# Ethernet_0.net
KiCad netlist of a schematic drawn in Altium Designer
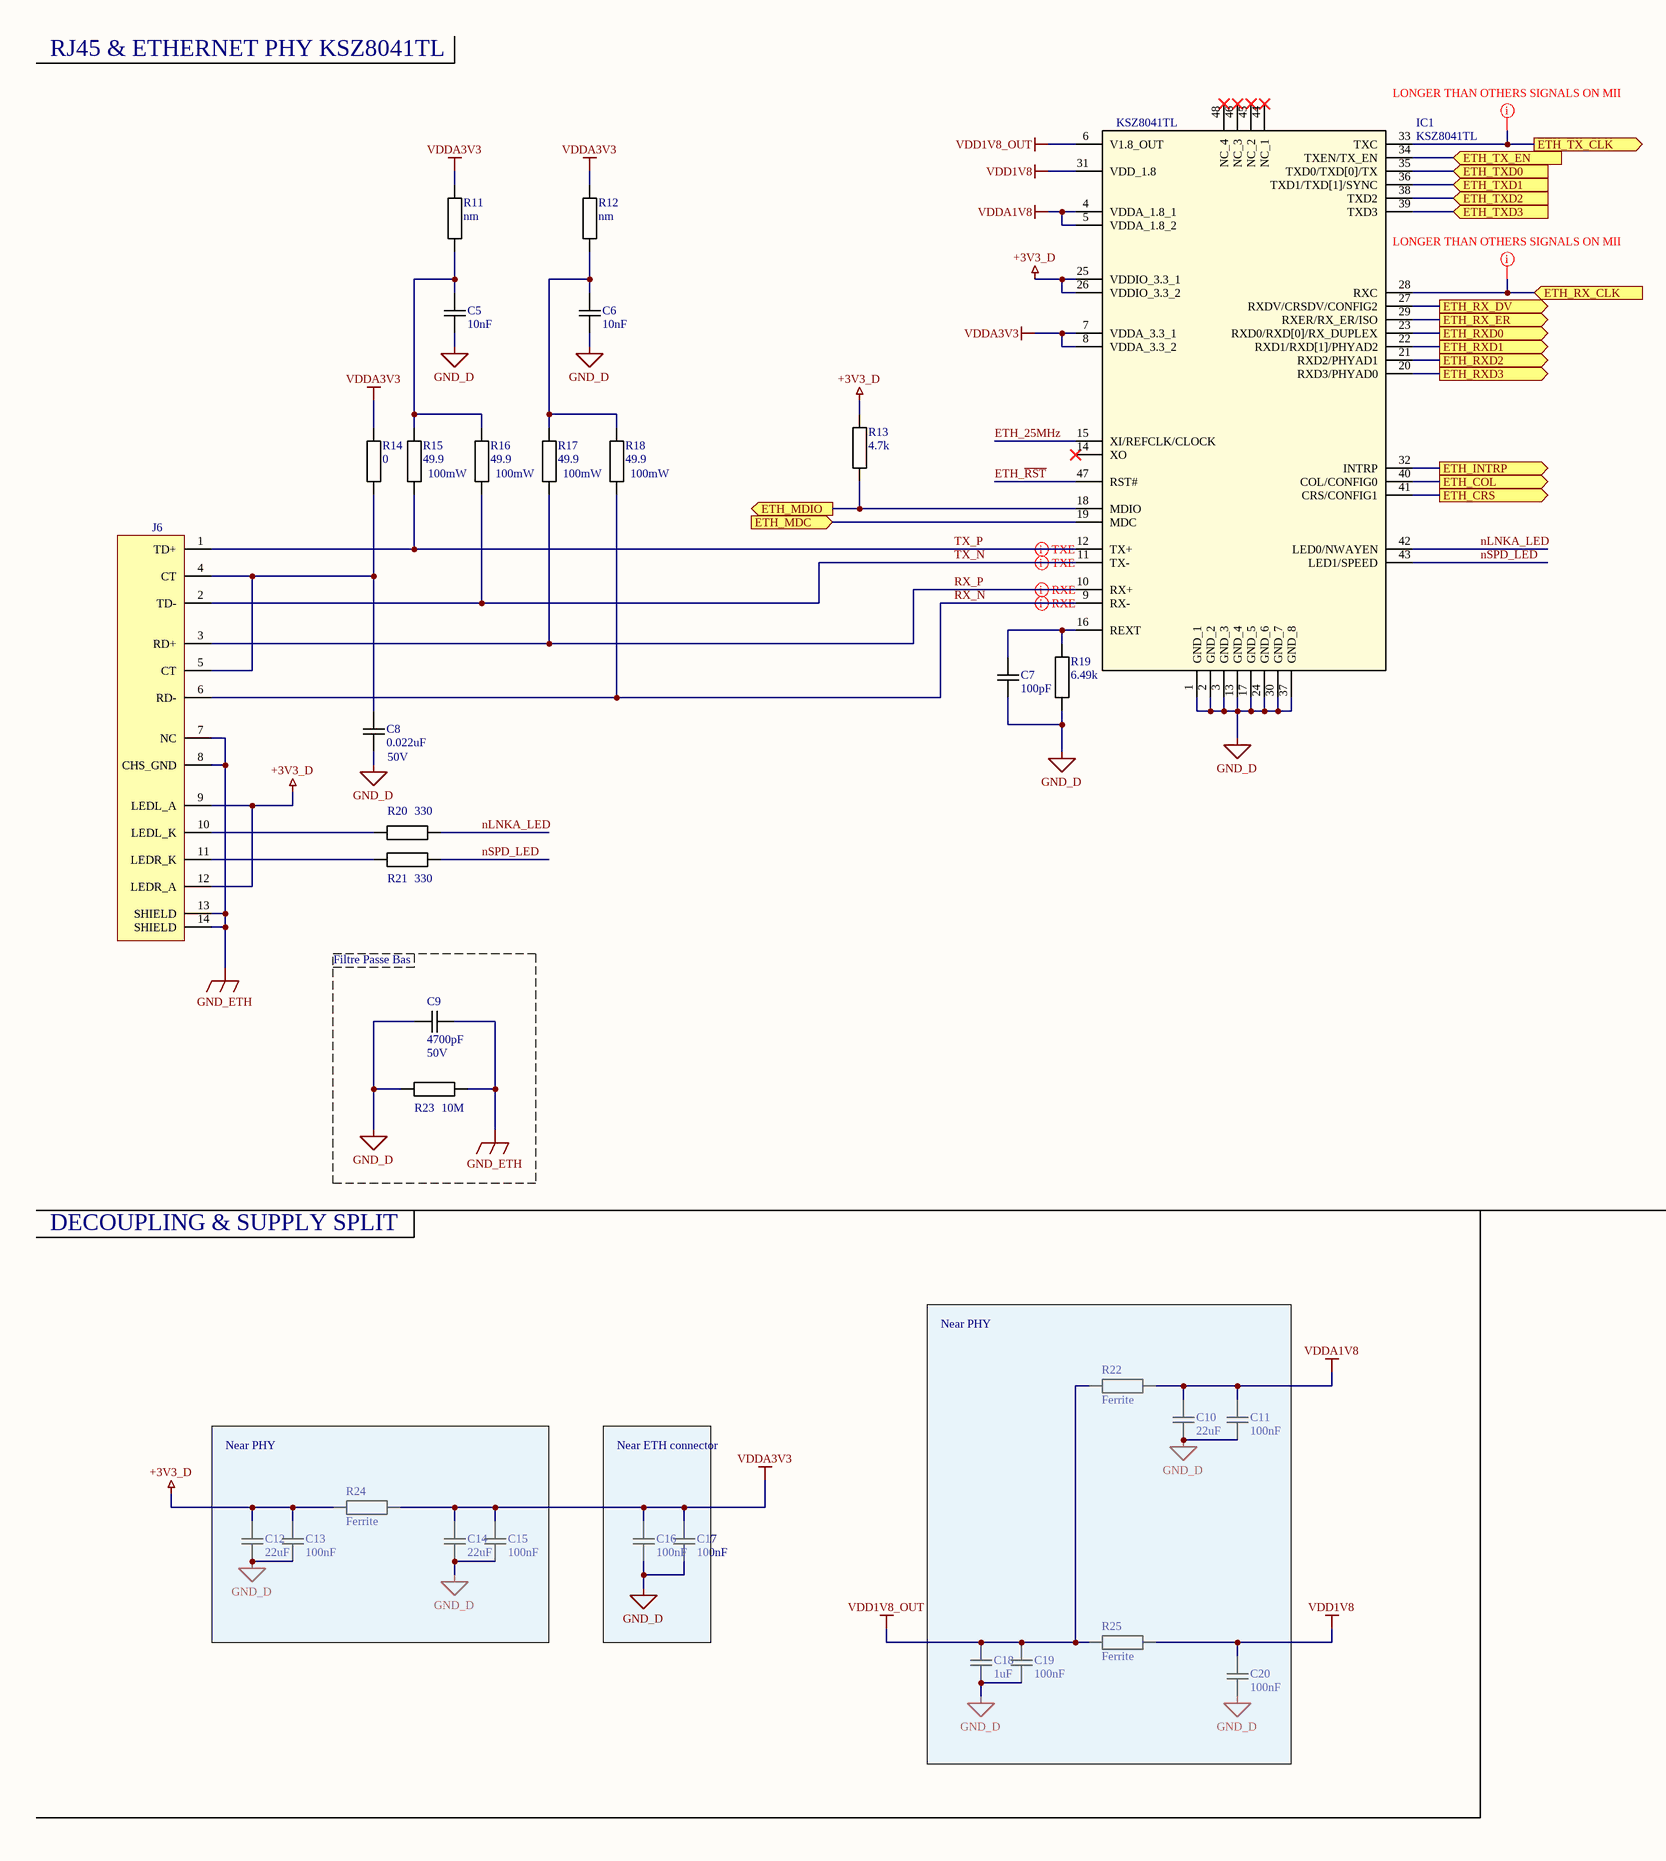
[diagram p0: Ethernet_0.SchDoc, left]
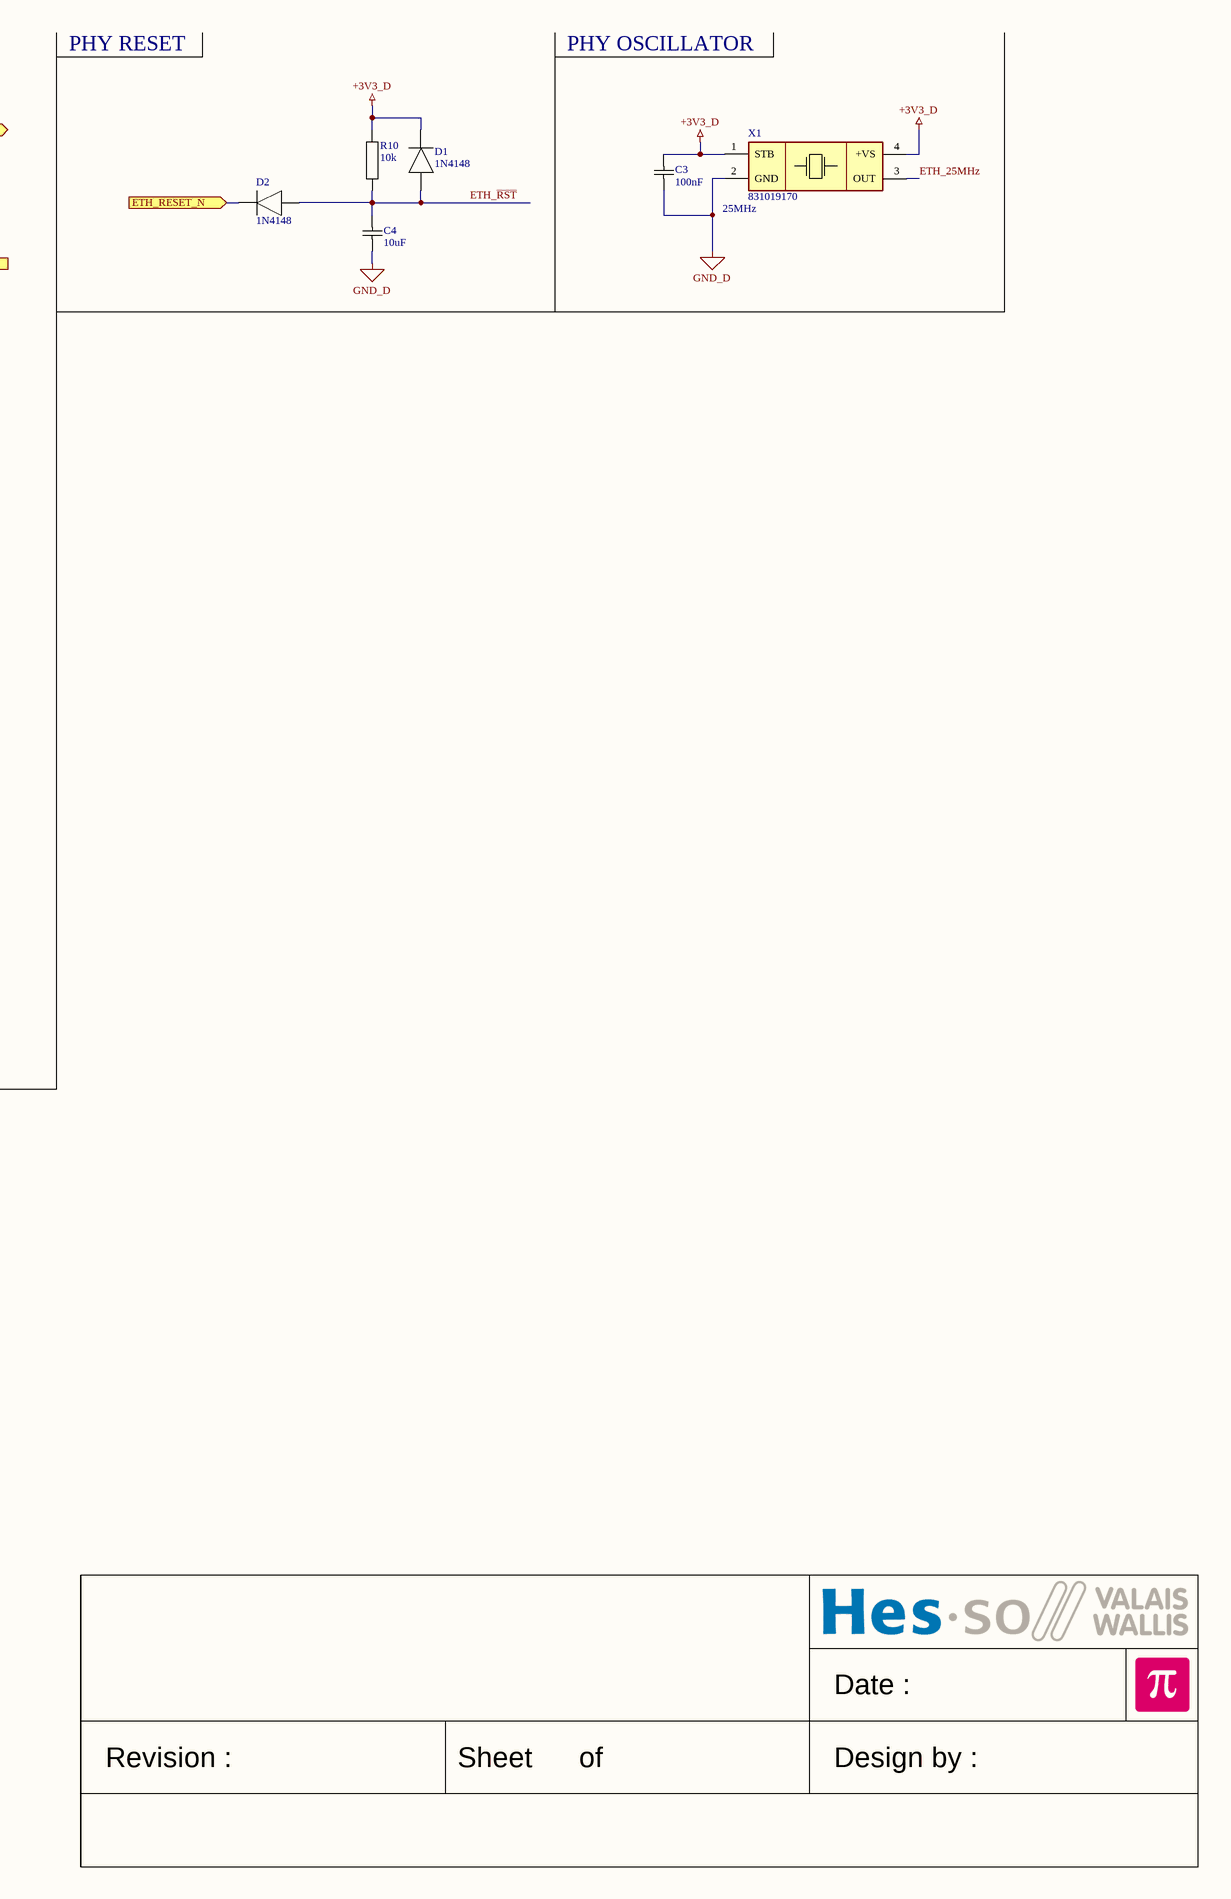
[diagram p1: Ethernet_0.SchDoc, right]

(export (version "E")
  (design (tool "Eeschema 10.0.6"))
  (components
    (comp (ref "C3")
      (value "100nF")
      (footprint "CAPACITOR 1608 REFLOW")
      (description "Capacitor X7R 10% 50V 1608(0603)")
      (libsource (lib "Capacitor") (part "Capacitor"))
    )
    (comp (ref "C4")
      (value "10uF")
      (footprint "CAPACITOR 2012 REFLOW")
      (description "Capacitor X7R 10% 50V 1608(0603)")
      (libsource (lib "Capacitor") (part "Capacitor"))
    )
    (comp (ref "C5")
      (value "10nF")
      (footprint "CAPACITOR 1608 REFLOW")
      (description "Capacitor X7R 10% 50V 1608(0603)")
      (libsource (lib "Capacitor") (part "Capacitor"))
    )
    (comp (ref "C6")
      (value "10nF")
      (footprint "CAPACITOR 1608 REFLOW")
      (description "Capacitor X7R 10% 50V 1608(0603)")
      (libsource (lib "Capacitor") (part "Capacitor"))
    )
    (comp (ref "C7")
      (value "100pF")
      (footprint "CAPACITOR 1608 REFLOW")
      (description "Capacitor X7R 10% 50V 1608(0603)")
      (libsource (lib "Capacitor") (part "Capacitor"))
    )
    (comp (ref "C8")
      (value "0.022uF")
      (footprint "CAPACITOR 1608 REFLOW")
      (description "Capacitor")
      (fields (field (name "V") "50V"))
      (libsource (lib "Capacitor") (part "Capacitor"))
    )
    (comp (ref "C9")
      (value "4700pF")
      (footprint "CAPACITOR 1608 REFLOW")
      (description "Capacitor")
      (fields (field (name "U") "50V"))
      (libsource (lib "Capacitor") (part "Capacitor"))
    )
    (comp (ref "C10")
      (value "22uF")
      (footprint "CAPACITOR 2012 REFLOW")
      (description "Capacitor X7R 10% 50V 1608(0603)")
      (libsource (lib "Capacitor") (part "Capacitor"))
    )
    (comp (ref "C11")
      (value "100nF")
      (footprint "CAPACITOR 1608 REFLOW")
      (description "Capacitor X7R 10% 50V 1608(0603)")
      (libsource (lib "Capacitor") (part "Capacitor"))
    )
    (comp (ref "C12")
      (value "22uF")
      (footprint "CAPACITOR 2012 REFLOW")
      (description "Capacitor X7R 10% 50V 1608(0603)")
      (libsource (lib "Capacitor") (part "Capacitor"))
    )
    (comp (ref "C13")
      (value "100nF")
      (footprint "CAPACITOR 1608 REFLOW")
      (description "Capacitor X7R 10% 50V 1608(0603)")
      (libsource (lib "Capacitor") (part "Capacitor"))
    )
    (comp (ref "C14")
      (value "22uF")
      (footprint "CAPACITOR 2012 REFLOW")
      (description "Capacitor X7R 10% 50V 1608(0603)")
      (libsource (lib "Capacitor") (part "Capacitor"))
    )
    (comp (ref "C15")
      (value "100nF")
      (footprint "CAPACITOR 1608 REFLOW")
      (description "Capacitor X7R 10% 50V 1608(0603)")
      (libsource (lib "Capacitor") (part "Capacitor"))
    )
    (comp (ref "C16")
      (value "100nF")
      (footprint "CAPACITOR 1608 REFLOW")
      (description "Capacitor X7R 10% 50V 1608(0603)")
      (libsource (lib "Capacitor") (part "Capacitor"))
    )
    (comp (ref "C17")
      (value "100nF")
      (footprint "CAPACITOR 1608 REFLOW")
      (description "Capacitor X7R 10% 50V 1608(0603)")
      (libsource (lib "Capacitor") (part "Capacitor"))
    )
    (comp (ref "C18")
      (value "1uF")
      (footprint "CAPACITOR 2012 REFLOW")
      (description "Capacitor X7R 10% 50V 1608(0603)")
      (libsource (lib "Capacitor") (part "Capacitor"))
    )
    (comp (ref "C19")
      (value "100nF")
      (footprint "CAPACITOR 1608 REFLOW")
      (description "Capacitor X7R 10% 50V 1608(0603)")
      (libsource (lib "Capacitor") (part "Capacitor"))
    )
    (comp (ref "C20")
      (value "100nF")
      (footprint "CAPACITOR 1608 REFLOW")
      (description "Capacitor X7R 10% 50V 1608(0603)")
      (libsource (lib "Capacitor") (part "Capacitor"))
    )
    (comp (ref "D1")
      (value "1N4148")
      (footprint "DIODE SOD323 REFLOW")
      (description "Diode generic 2 leads")
      (libsource (lib "Diode") (part "DIODE"))
    )
    (comp (ref "D2")
      (value "1N4148")
      (footprint "DIODE SOD323 REFLOW")
      (description "Diode generic 2 leads")
      (libsource (lib "Diode") (part "DIODE"))
    )
    (comp (ref "IC1")
      (value "KSZ8041TL")
      (footprint "SamacSys:QFP50P900X900X105-48N")
      (description "Integrated Circuit")
      (fields
        (field (name "MANUFACTURER_PART_NUMBER") "KSZ8041TL")
        (field (name "MOUSER PART NUMBER") "998-KSZ8041TL")
      )
      (libsource (lib "SamacSys") (part "KSZ8041TL"))
    )
    (comp (ref "J6")
      (value "RJ45-PULSE-J0011D21BNL")
      (footprint "RJ45 PULSE J0011D21BNL")
      (description "Integrated connector modules 10/100 base-TX belMag with LEDs")
      (libsource (lib "Connector") (part "RJ45 PULSE J0011D21BNL"))
    )
    (comp (ref "R10")
      (value "10k")
      (footprint "RESISTOR 1608 REFLOW")
      (description "Resistor 1% 50V 100mW 1608(0603)")
      (libsource (lib "Resistor") (part "Resistor"))
    )
    (comp (ref "R11")
      (value "nm")
      (footprint "RESISTOR 1608 REFLOW")
      (description "Resistor")
      (libsource (lib "Resistor") (part "Resistor"))
    )
    (comp (ref "R12")
      (value "nm")
      (footprint "RESISTOR 1608 REFLOW")
      (description "Resistor")
      (libsource (lib "Resistor") (part "Resistor"))
    )
    (comp (ref "R13")
      (value "4.7k")
      (footprint "RESISTOR 1608 REFLOW")
      (description "Resistor 1% 50V 100mW 1608(0603)")
      (libsource (lib "Resistor") (part "Resistor"))
    )
    (comp (ref "R14")
      (value "0")
      (footprint "RESISTOR 1608 REFLOW")
      (description "Resistor")
      (libsource (lib "Resistor") (part "Resistor"))
    )
    (comp (ref "R15")
      (value "49.9")
      (footprint "RESISTOR 1608 REFLOW")
      (description "Resistor")
      (fields (field (name "W") "100mW"))
      (libsource (lib "Resistor") (part "Resistor"))
    )
    (comp (ref "R16")
      (value "49.9")
      (footprint "RESISTOR 1608 REFLOW")
      (description "Resistor")
      (fields (field (name "W") "100mW"))
      (libsource (lib "Resistor") (part "Resistor"))
    )
    (comp (ref "R17")
      (value "49.9")
      (footprint "RESISTOR 1608 REFLOW")
      (description "Resistor")
      (fields (field (name "W") "100mW"))
      (libsource (lib "Resistor") (part "Resistor"))
    )
    (comp (ref "R18")
      (value "49.9")
      (footprint "RESISTOR 1608 REFLOW")
      (description "Resistor")
      (fields (field (name "W") "100mW"))
      (libsource (lib "Resistor") (part "Resistor"))
    )
    (comp (ref "R19")
      (value "6.49k")
      (footprint "RESISTOR 1608 REFLOW")
      (description "Resistor 1% 50V 100mW 1608(0603)")
      (libsource (lib "Resistor") (part "Resistor"))
    )
    (comp (ref "R20")
      (value "330")
      (footprint "RESISTOR 1608 REFLOW")
      (description "Resistor")
      (libsource (lib "Resistor") (part "Resistor"))
    )
    (comp (ref "R21")
      (value "330")
      (footprint "RESISTOR 1608 REFLOW")
      (description "Resistor")
      (libsource (lib "Resistor") (part "Resistor"))
    )
    (comp (ref "R22")
      (value "Ferrite")
      (footprint "RESISTOR 1608 REFLOW")
      (description "Resistor 1% 50V 100mW 1608(0603)")
      (libsource (lib "Resistor") (part "Resistor"))
    )
    (comp (ref "R23")
      (value "10M")
      (footprint "RESISTOR 1608 REFLOW")
      (description "Resistor")
      (libsource (lib "Resistor") (part "Resistor"))
    )
    (comp (ref "R24")
      (value "Ferrite")
      (footprint "RESISTOR 1608 REFLOW")
      (description "Resistor 1% 50V 100mW 1608(0603)")
      (libsource (lib "Resistor") (part "Resistor"))
    )
    (comp (ref "R25")
      (value "Ferrite")
      (footprint "RESISTOR 1608 REFLOW")
      (description "Resistor 1% 50V 100mW 1608(0603)")
      (libsource (lib "Resistor") (part "Resistor"))
    )
    (comp (ref "X1")
      (value "831019170")
      (footprint "Oscillator C5.2x7.2 IQD LFSPXO")
      (description "Oscillator C5.2x7.2 IQD LFSPXO")
      (fields (field (name "FREQ") "25MHz"))
      (libsource (lib "Oscillator") (part "Oscillator C5.2x7.2 IQD LFSPXO"))
    )
  )
  (nets
    (net (code "1") (name "+3V3_D") (class "Default")
      (node (ref "C12") (pin "2") (pinfunction "2_2") (pintype "passive"))
      (node (ref "C13") (pin "2") (pinfunction "2_2") (pintype "passive"))
      (node (ref "C3") (pin "2") (pinfunction "2_2") (pintype "passive"))
      (node (ref "D1") (pin "1") (pinfunction "C_1") (pintype "passive"))
      (node (ref "IC1") (pin "25") (pinfunction "VDDIO_3.3_1_25") (pintype "passive"))
      (node (ref "IC1") (pin "26") (pinfunction "VDDIO_3.3_2_26") (pintype "passive"))
      (node (ref "J6") (pin "12") (pinfunction "LEDR_A_12") (pintype "passive"))
      (node (ref "J6") (pin "9") (pinfunction "LEDL_A_9") (pintype "passive"))
      (node (ref "R10") (pin "2") (pinfunction "2_2") (pintype "passive"))
      (node (ref "R13") (pin "2") (pinfunction "2_2") (pintype "passive"))
      (node (ref "R24") (pin "2") (pinfunction "2_2") (pintype "passive"))
      (node (ref "X1") (pin "1") (pinfunction "STB_1") (pintype "passive"))
      (node (ref "X1") (pin "4") (pinfunction "+VS_4") (pintype "passive"))
    )
    (net (code "2") (name "/ETH_25MHz") (class "Default")
      (node (ref "IC1") (pin "15") (pinfunction "XI/REFCLK/CLOCK_15") (pintype "passive"))
      (node (ref "X1") (pin "3") (pinfunction "OUT_3") (pintype "passive"))
    )
    (net (code "3") (name "/ETH_COL") (class "Default")
      (node (ref "IC1") (pin "40") (pinfunction "COL/CONFIG0_40") (pintype "passive"))
    )
    (net (code "4") (name "/ETH_CRS") (class "Default")
      (node (ref "IC1") (pin "41") (pinfunction "CRS/CONFIG1_41") (pintype "passive"))
    )
    (net (code "5") (name "/ETH_INTRP") (class "Default")
      (node (ref "IC1") (pin "32") (pinfunction "INTRP_32") (pintype "passive"))
    )
    (net (code "6") (name "/ETH_MDC") (class "Default")
      (node (ref "IC1") (pin "19") (pinfunction "MDC_19") (pintype "passive"))
    )
    (net (code "7") (name "/ETH_MDIO") (class "Default")
      (node (ref "IC1") (pin "18") (pinfunction "MDIO_18") (pintype "passive"))
      (node (ref "R13") (pin "1") (pinfunction "1_1") (pintype "passive"))
    )
    (net (code "8") (name "/ETH_RESET_N") (class "Default")
      (node (ref "D2") (pin "1") (pinfunction "C_1") (pintype "passive"))
    )
    (net (code "9") (name "/ETH_RXD0") (class "Default")
      (node (ref "IC1") (pin "23") (pinfunction "RXD0/RXD[0]/RX_DUPLEX_23") (pintype "passive"))
    )
    (net (code "10") (name "/ETH_RXD1") (class "Default")
      (node (ref "IC1") (pin "22") (pinfunction "RXD1/RXD[1]/PHYAD2_22") (pintype "passive"))
    )
    (net (code "11") (name "/ETH_RXD2") (class "Default")
      (node (ref "IC1") (pin "21") (pinfunction "RXD2/PHYAD1_21") (pintype "passive"))
    )
    (net (code "12") (name "/ETH_RXD3") (class "Default")
      (node (ref "IC1") (pin "20") (pinfunction "RXD3/PHYAD0_20") (pintype "passive"))
    )
    (net (code "13") (name "/ETH_RX_CLK") (class "Default")
      (node (ref "IC1") (pin "28") (pinfunction "RXC_28") (pintype "passive"))
    )
    (net (code "14") (name "/ETH_RX_DV") (class "Default")
      (node (ref "IC1") (pin "27") (pinfunction "RXDV/CRSDV/CONFIG2_27") (pintype "passive"))
    )
    (net (code "15") (name "/ETH_RX_ER") (class "Default")
      (node (ref "IC1") (pin "29") (pinfunction "RXER/RX_ER/ISO_29") (pintype "passive"))
    )
    (net (code "16") (name "/ETH_TXD0") (class "Default")
      (node (ref "IC1") (pin "35") (pinfunction "TXD0/TXD[0]/TX_35") (pintype "passive"))
    )
    (net (code "17") (name "/ETH_TXD1") (class "Default")
      (node (ref "IC1") (pin "36") (pinfunction "TXD1/TXD[1]/SYNC_36") (pintype "passive"))
    )
    (net (code "18") (name "/ETH_TXD2") (class "Default")
      (node (ref "IC1") (pin "38") (pinfunction "TXD2_38") (pintype "passive"))
    )
    (net (code "19") (name "/ETH_TXD3") (class "Default")
      (node (ref "IC1") (pin "39") (pinfunction "TXD3_39") (pintype "passive"))
    )
    (net (code "20") (name "/ETH_TX_CLK") (class "Default")
      (node (ref "IC1") (pin "33") (pinfunction "TXC_33") (pintype "passive"))
    )
    (net (code "21") (name "/ETH_TX_EN") (class "Default")
      (node (ref "IC1") (pin "34") (pinfunction "TXEN/TX_EN_34") (pintype "passive"))
    )
    (net (code "22") (name "/ETH_~{RST}") (class "Default")
      (node (ref "C4") (pin "2") (pinfunction "2_2") (pintype "passive"))
      (node (ref "D1") (pin "2") (pinfunction "A_2") (pintype "passive"))
      (node (ref "D2") (pin "2") (pinfunction "A_2") (pintype "passive"))
      (node (ref "IC1") (pin "47") (pinfunction "RST#_47") (pintype "passive"))
      (node (ref "R10") (pin "1") (pinfunction "1_1") (pintype "passive"))
    )
    (net (code "23") (name "/RX_N") (class "Default")
      (node (ref "IC1") (pin "9") (pinfunction "RX-_9") (pintype "passive"))
      (node (ref "J6") (pin "6") (pinfunction "RD-_6") (pintype "passive"))
      (node (ref "R18") (pin "1") (pinfunction "1_1") (pintype "passive"))
    )
    (net (code "24") (name "/RX_P") (class "Default")
      (node (ref "IC1") (pin "10") (pinfunction "RX+_10") (pintype "passive"))
      (node (ref "J6") (pin "3") (pinfunction "RD+_3") (pintype "passive"))
      (node (ref "R17") (pin "1") (pinfunction "1_1") (pintype "passive"))
    )
    (net (code "25") (name "/TX_N") (class "Default")
      (node (ref "IC1") (pin "11") (pinfunction "TX-_11") (pintype "passive"))
      (node (ref "J6") (pin "2") (pinfunction "TD-_2") (pintype "passive"))
      (node (ref "R16") (pin "1") (pinfunction "1_1") (pintype "passive"))
    )
    (net (code "26") (name "/TX_P") (class "Default")
      (node (ref "IC1") (pin "12") (pinfunction "TX+_12") (pintype "passive"))
      (node (ref "J6") (pin "1") (pinfunction "TD+_1") (pintype "passive"))
      (node (ref "R15") (pin "1") (pinfunction "1_1") (pintype "passive"))
    )
    (net (code "27") (name "/nLNKA_LED") (class "Default")
      (node (ref "IC1") (pin "42") (pinfunction "LED0/NWAYEN_42") (pintype "passive"))
      (node (ref "R20") (pin "1") (pinfunction "1_1") (pintype "passive"))
    )
    (net (code "28") (name "/nSPD_LED") (class "Default")
      (node (ref "IC1") (pin "43") (pinfunction "LED1/SPEED_43") (pintype "passive"))
      (node (ref "R21") (pin "1") (pinfunction "1_1") (pintype "passive"))
    )
    (net (code "29") (name "GND_D") (class "Default")
      (node (ref "C10") (pin "1") (pinfunction "1_1") (pintype "passive"))
      (node (ref "C11") (pin "1") (pinfunction "1_1") (pintype "passive"))
      (node (ref "C12") (pin "1") (pinfunction "1_1") (pintype "passive"))
      (node (ref "C13") (pin "1") (pinfunction "1_1") (pintype "passive"))
      (node (ref "C14") (pin "1") (pinfunction "1_1") (pintype "passive"))
      (node (ref "C15") (pin "1") (pinfunction "1_1") (pintype "passive"))
      (node (ref "C16") (pin "1") (pinfunction "1_1") (pintype "passive"))
      (node (ref "C17") (pin "1") (pinfunction "1_1") (pintype "passive"))
      (node (ref "C18") (pin "1") (pinfunction "1_1") (pintype "passive"))
      (node (ref "C19") (pin "1") (pinfunction "1_1") (pintype "passive"))
      (node (ref "C20") (pin "1") (pinfunction "1_1") (pintype "passive"))
      (node (ref "C3") (pin "1") (pinfunction "1_1") (pintype "passive"))
      (node (ref "C4") (pin "1") (pinfunction "1_1") (pintype "passive"))
      (node (ref "C5") (pin "1") (pinfunction "1_1") (pintype "passive"))
      (node (ref "C6") (pin "1") (pinfunction "1_1") (pintype "passive"))
      (node (ref "C7") (pin "1") (pinfunction "1_1") (pintype "passive"))
      (node (ref "C8") (pin "2") (pinfunction "2_2") (pintype "passive"))
      (node (ref "C9") (pin "1") (pinfunction "1_1") (pintype "passive"))
      (node (ref "IC1") (pin "1") (pinfunction "GND_1_1") (pintype "passive"))
      (node (ref "IC1") (pin "13") (pinfunction "GND_4_13") (pintype "passive"))
      (node (ref "IC1") (pin "17") (pinfunction "GND_5_17") (pintype "passive"))
      (node (ref "IC1") (pin "2") (pinfunction "GND_2_2") (pintype "passive"))
      (node (ref "IC1") (pin "24") (pinfunction "GND_6_24") (pintype "passive"))
      (node (ref "IC1") (pin "3") (pinfunction "GND_3_3") (pintype "passive"))
      (node (ref "IC1") (pin "30") (pinfunction "GND_7_30") (pintype "passive"))
      (node (ref "IC1") (pin "37") (pinfunction "GND_8_37") (pintype "passive"))
      (node (ref "R19") (pin "1") (pinfunction "1_1") (pintype "passive"))
      (node (ref "R23") (pin "2") (pinfunction "2_2") (pintype "passive"))
      (node (ref "X1") (pin "2") (pinfunction "GND_2") (pintype "passive"))
    )
    (net (code "30") (name "GND_ETH") (class "Default")
      (node (ref "C9") (pin "2") (pinfunction "2_2") (pintype "passive"))
      (node (ref "J6") (pin "13") (pinfunction "SHIELD_13") (pintype "passive"))
      (node (ref "J6") (pin "14") (pinfunction "SHIELD_14") (pintype "passive"))
      (node (ref "J6") (pin "7") (pinfunction "NC_7") (pintype "passive"))
      (node (ref "J6") (pin "8") (pinfunction "CHS_GND_8") (pintype "passive"))
      (node (ref "R23") (pin "1") (pinfunction "1_1") (pintype "passive"))
    )
    (net (code "31") (name "Net-(C5-Pad2)") (class "Default")
      (node (ref "C5") (pin "2") (pinfunction "2_2") (pintype "passive"))
      (node (ref "R11") (pin "1") (pinfunction "1_1") (pintype "passive"))
      (node (ref "R15") (pin "2") (pinfunction "2_2") (pintype "passive"))
      (node (ref "R16") (pin "2") (pinfunction "2_2") (pintype "passive"))
    )
    (net (code "32") (name "Net-(C6-Pad2)") (class "Default")
      (node (ref "C6") (pin "2") (pinfunction "2_2") (pintype "passive"))
      (node (ref "R12") (pin "1") (pinfunction "1_1") (pintype "passive"))
      (node (ref "R17") (pin "2") (pinfunction "2_2") (pintype "passive"))
      (node (ref "R18") (pin "2") (pinfunction "2_2") (pintype "passive"))
    )
    (net (code "33") (name "Net-(C8-Pad1)") (class "Default")
      (node (ref "C8") (pin "1") (pinfunction "1_1") (pintype "passive"))
      (node (ref "J6") (pin "4") (pinfunction "CT_4") (pintype "passive"))
      (node (ref "J6") (pin "5") (pinfunction "CT_5") (pintype "passive"))
      (node (ref "R14") (pin "1") (pinfunction "1_1") (pintype "passive"))
    )
    (net (code "34") (name "Net-(IC1-REXT)") (class "Default")
      (node (ref "C7") (pin "2") (pinfunction "2_2") (pintype "passive"))
      (node (ref "IC1") (pin "16") (pinfunction "REXT_16") (pintype "passive"))
      (node (ref "R19") (pin "2") (pinfunction "2_2") (pintype "passive"))
    )
    (net (code "35") (name "Net-(J6-LEDL_K)") (class "Default")
      (node (ref "J6") (pin "10") (pinfunction "LEDL_K_10") (pintype "passive"))
      (node (ref "R20") (pin "2") (pinfunction "2_2") (pintype "passive"))
    )
    (net (code "36") (name "Net-(J6-LEDR_K)") (class "Default")
      (node (ref "J6") (pin "11") (pinfunction "LEDR_K_11") (pintype "passive"))
      (node (ref "R21") (pin "2") (pinfunction "2_2") (pintype "passive"))
    )
    (net (code "37") (name "VDD1V8") (class "Default")
      (node (ref "C20") (pin "2") (pinfunction "2_2") (pintype "passive"))
      (node (ref "IC1") (pin "31") (pinfunction "VDD_1.8_31") (pintype "passive"))
      (node (ref "R25") (pin "1") (pinfunction "1_1") (pintype "passive"))
    )
    (net (code "38") (name "VDD1V8_OUT") (class "Default")
      (node (ref "C18") (pin "2") (pinfunction "2_2") (pintype "passive"))
      (node (ref "C19") (pin "2") (pinfunction "2_2") (pintype "passive"))
      (node (ref "IC1") (pin "6") (pinfunction "V1.8_OUT_6") (pintype "passive"))
      (node (ref "R22") (pin "2") (pinfunction "2_2") (pintype "passive"))
      (node (ref "R25") (pin "2") (pinfunction "2_2") (pintype "passive"))
    )
    (net (code "39") (name "VDDA1V8") (class "Default")
      (node (ref "C10") (pin "2") (pinfunction "2_2") (pintype "passive"))
      (node (ref "C11") (pin "2") (pinfunction "2_2") (pintype "passive"))
      (node (ref "IC1") (pin "4") (pinfunction "VDDA_1.8_1_4") (pintype "passive"))
      (node (ref "IC1") (pin "5") (pinfunction "VDDA_1.8_2_5") (pintype "passive"))
      (node (ref "R22") (pin "1") (pinfunction "1_1") (pintype "passive"))
    )
    (net (code "40") (name "VDDA3V3") (class "Default")
      (node (ref "C14") (pin "2") (pinfunction "2_2") (pintype "passive"))
      (node (ref "C15") (pin "2") (pinfunction "2_2") (pintype "passive"))
      (node (ref "C16") (pin "2") (pinfunction "2_2") (pintype "passive"))
      (node (ref "C17") (pin "2") (pinfunction "2_2") (pintype "passive"))
      (node (ref "IC1") (pin "7") (pinfunction "VDDA_3.3_1_7") (pintype "passive"))
      (node (ref "IC1") (pin "8") (pinfunction "VDDA_3.3_2_8") (pintype "passive"))
      (node (ref "R11") (pin "2") (pinfunction "2_2") (pintype "passive"))
      (node (ref "R12") (pin "2") (pinfunction "2_2") (pintype "passive"))
      (node (ref "R14") (pin "2") (pinfunction "2_2") (pintype "passive"))
      (node (ref "R24") (pin "1") (pinfunction "1_1") (pintype "passive"))
    )
    (net (code "41") (name "unconnected-(IC1-NC_1-Pad44)") (class "Default")
      (node (ref "IC1") (pin "44") (pinfunction "NC_1_44") (pintype "passive+no_connect"))
    )
    (net (code "42") (name "unconnected-(IC1-NC_2-Pad45)") (class "Default")
      (node (ref "IC1") (pin "45") (pinfunction "NC_2_45") (pintype "passive+no_connect"))
    )
    (net (code "43") (name "unconnected-(IC1-NC_3-Pad46)") (class "Default")
      (node (ref "IC1") (pin "46") (pinfunction "NC_3_46") (pintype "passive+no_connect"))
    )
    (net (code "44") (name "unconnected-(IC1-NC_4-Pad48)") (class "Default")
      (node (ref "IC1") (pin "48") (pinfunction "NC_4_48") (pintype "passive+no_connect"))
    )
    (net (code "45") (name "unconnected-(IC1-XO-Pad14)") (class "Default")
      (node (ref "IC1") (pin "14") (pinfunction "XO_14") (pintype "passive+no_connect"))
    )
  )
)
